# PERIPHERAL.net
KiCad netlist of a schematic drawn in Altium Designer
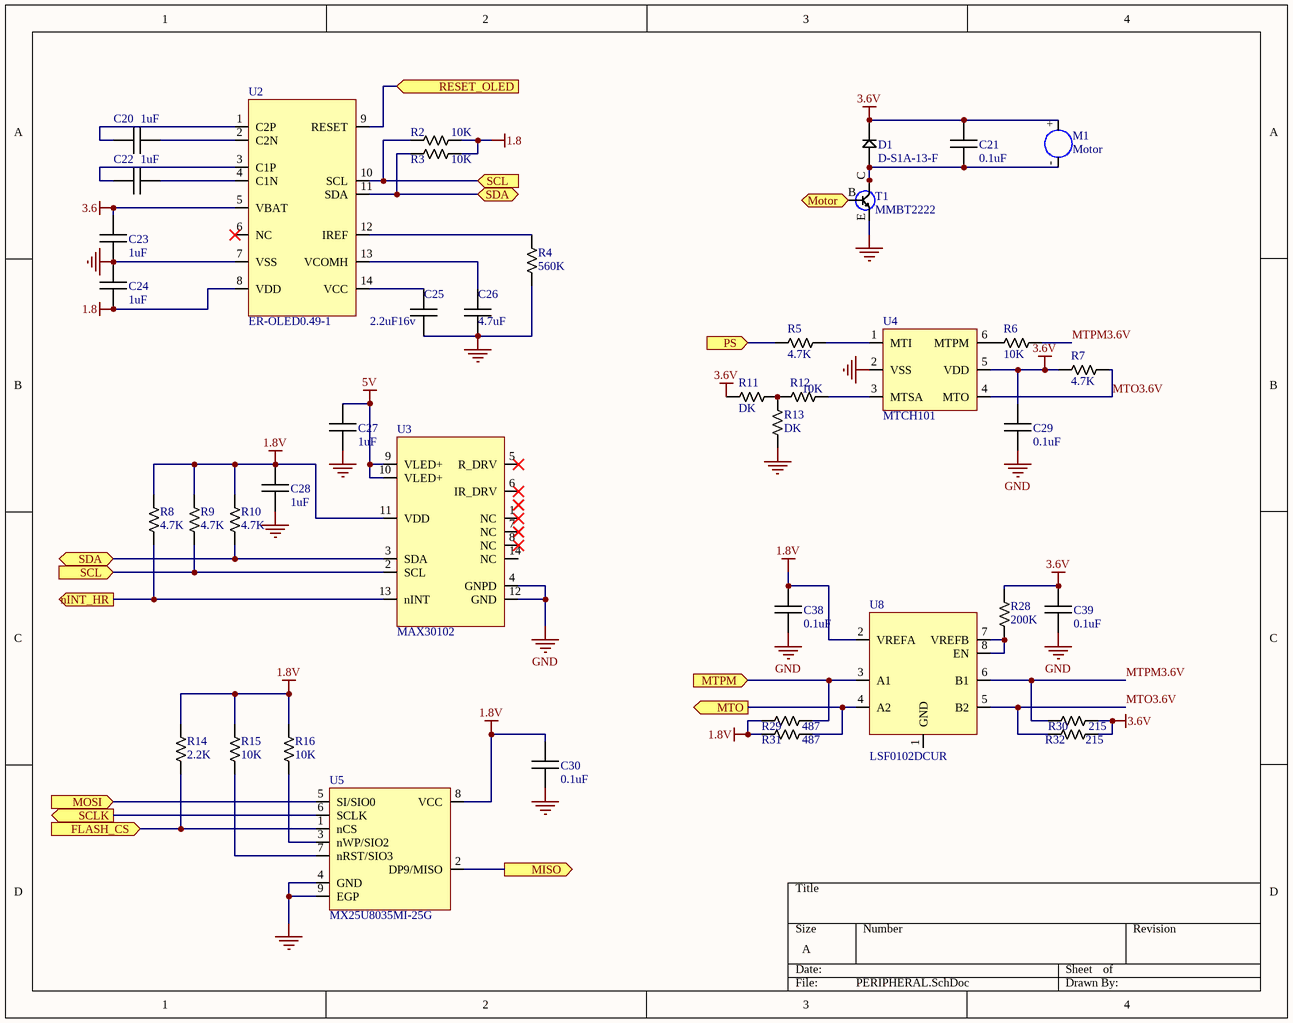
[diagram p0: PERIPHERAL.SchDoc]

(export (version "E")
  (design (tool "Eeschema 10.0.6"))
  (components
    (comp (ref "C20")
      (value "1uF")
      (description "SMD_CAPACITOR")
      (fields (field (name "DIGI-KEY PART NUMBER") "490-3890-1-ND") (field (name "TOLERANCE") "±10%"))
      (libsource (lib "test") (part "C1uF_0402"))
    )
    (comp (ref "C21")
      (value "0.1uF")
      (description "SMD_CAPACITOR")
      (fields (field (name "DIGI-KEY PART NUMBER") "490-6319-1-ND") (field (name "TOLERANCE") "±10%"))
      (libsource (lib "test") (part "C0.1uF_0402"))
    )
    (comp (ref "C22")
      (value "1uF")
      (description "SMD_CAPACITOR")
      (fields (field (name "DIGI-KEY PART NUMBER") "490-3890-1-ND") (field (name "TOLERANCE") "±10%"))
      (libsource (lib "test") (part "C1uF_0402"))
    )
    (comp (ref "C23")
      (value "1uF")
      (description "SMD_CAPACITOR")
      (fields (field (name "DIGI-KEY PART NUMBER") "490-3890-1-ND") (field (name "TOLERANCE") "±10%"))
      (libsource (lib "test") (part "C1uF_0402"))
    )
    (comp (ref "C24")
      (value "1uF")
      (description "SMD_CAPACITOR")
      (fields (field (name "DIGI-KEY PART NUMBER") "490-3890-1-ND") (field (name "TOLERANCE") "±10%"))
      (libsource (lib "test") (part "C1uF_0402"))
    )
    (comp (ref "C25")
      (value "2.2uF16v")
      (description "SMD_CAPACITOR")
      (fields (field (name "DIGI-KEY PART NUMBER") "490-3906-1-ND") (field (name "TOLERANCE") "±10%"))
      (libsource (lib "HR_lib") (part "C2.2uF_0805"))
    )
    (comp (ref "C26")
      (value "4.7uF")
      (description "SMD_CAPACITOR")
      (fields (field (name "DIGI-KEY PART NUMBER") "445-1385-1-ND") (field (name "TOLERANCE") "±10%"))
      (libsource (lib "HR_lib") (part "C4.7uF_0805"))
    )
    (comp (ref "C27")
      (value "1uF")
      (description "SMD_CAPACITOR")
      (fields (field (name "DIGI-KEY PART NUMBER") "490-3890-1-ND") (field (name "TOLERANCE") "±10%"))
      (libsource (lib "test") (part "C1uF_0402"))
    )
    (comp (ref "C28")
      (value "1uF")
      (description "SMD_CAPACITOR")
      (fields (field (name "DIGI-KEY PART NUMBER") "490-3890-1-ND") (field (name "TOLERANCE") "±10%"))
      (libsource (lib "test") (part "C1uF_0402"))
    )
    (comp (ref "C29")
      (value "0.1uF")
      (description "SMD_CAPACITOR")
      (fields (field (name "DIGI-KEY PART NUMBER") "490-6319-1-ND") (field (name "TOLERANCE") "±10%"))
      (libsource (lib "test") (part "C0.1uF_0402"))
    )
    (comp (ref "C30")
      (value "0.1uF")
      (description "SMD_CAPACITOR")
      (fields (field (name "DIGI-KEY PART NUMBER") "490-6319-1-ND") (field (name "TOLERANCE") "±10%"))
      (libsource (lib "test") (part "C0.1uF_0402"))
    )
    (comp (ref "C38")
      (value "0.1uF")
      (description "SMD_CAPACITOR")
      (fields (field (name "DIGI-KEY PART NUMBER") "490-6319-1-ND") (field (name "TOLERANCE") "±10%"))
      (libsource (lib "test") (part "C0.1uF_0402"))
    )
    (comp (ref "C39")
      (value "0.1uF")
      (description "SMD_CAPACITOR")
      (fields (field (name "DIGI-KEY PART NUMBER") "490-6319-1-ND") (field (name "TOLERANCE") "±10%"))
      (libsource (lib "test") (part "C0.1uF_0402"))
    )
    (comp (ref "D1")
      (value "D-S1A-13-F")
      (description "DIODE GEN PURP 50V 1A SMA")
      (libsource (lib "HR_lib") (part "D-S1A-13-F"))
    )
    (comp (ref "M1")
      (value "Motor")
      (description "vibrator coin 7mm")
      (fields (field (name "DIGI-KEY PART NUMBER") "1670-1000-ND"))
      (libsource (lib "HR_lib") (part "Motor"))
    )
    (comp (ref "R2")
      (value "10K")
      (footprint "R0603")
      (description "SMD_RESISTOR")
      (fields (field (name "DIGI-KEY PART NUMBER") "311-10KNCT-ND") (field (name "TOLERANCE") "±5%"))
      (libsource (lib "test") (part "R10K_0201"))
    )
    (comp (ref "R3")
      (value "10K")
      (footprint "R0603")
      (description "SMD_RESISTOR")
      (fields (field (name "DIGI-KEY PART NUMBER") "311-10KNCT-ND") (field (name "TOLERANCE") "±5%"))
      (libsource (lib "test") (part "R10K_0201"))
    )
    (comp (ref "R4")
      (value "560K")
      (footprint "R0603")
      (description "SMD_RESISTOR")
      (fields (field (name "DIGI-KEY PART NUMBER") "311-560KJRCT-ND") (field (name "TOLERANCE") "±5%"))
      (libsource (lib "test") (part "R560K_0402"))
    )
    (comp (ref "R5")
      (value "4.7K")
      (footprint "0603:R0603")
      (description "SMD_RESISTOR")
      (fields (field (name "DIGI-KEY PART NUMBER") "311-4.7KLRCT-ND") (field (name "TOLERANCE") "±1%"))
      (libsource (lib "HR_lib") (part "R4.7K_0402"))
    )
    (comp (ref "R6")
      (value "10K")
      (footprint "0603:R0603")
      (description "SMD_RESISTOR")
      (fields (field (name "DIGI-KEY PART NUMBER") "311-10KNCT-ND") (field (name "TOLERANCE") "±5%"))
      (libsource (lib "HR_lib") (part "R10K_0201"))
    )
    (comp (ref "R7")
      (value "4.7K")
      (footprint "0603:R0603")
      (description "SMD_RESISTOR")
      (fields (field (name "DIGI-KEY PART NUMBER") "311-4.7KLRCT-ND") (field (name "TOLERANCE") "±1%"))
      (libsource (lib "HR_lib") (part "R4.7K_0402"))
    )
    (comp (ref "R8")
      (value "4.7K")
      (footprint "0603:R0603")
      (description "SMD_RESISTOR")
      (fields (field (name "DIGI-KEY PART NUMBER") "311-4.7KLRCT-ND") (field (name "TOLERANCE") "±1%"))
      (libsource (lib "HR_lib") (part "R4.7K_0402"))
    )
    (comp (ref "R9")
      (value "4.7K")
      (footprint "0603:R0603")
      (description "SMD_RESISTOR")
      (fields (field (name "DIGI-KEY PART NUMBER") "311-4.7KLRCT-ND") (field (name "TOLERANCE") "±1%"))
      (libsource (lib "HR_lib") (part "R4.7K_0402"))
    )
    (comp (ref "R10")
      (value "4.7K")
      (footprint "0603:R0603")
      (description "SMD_RESISTOR")
      (fields (field (name "DIGI-KEY PART NUMBER") "311-4.7KLRCT-ND") (field (name "TOLERANCE") "±1%"))
      (libsource (lib "HR_lib") (part "R4.7K_0402"))
    )
    (comp (ref "R11")
      (value "DK")
      (footprint "0603:R0603")
      (description "SMD_RESISTOR")
      (libsource (lib "HR_lib") (part "RDK_0402"))
    )
    (comp (ref "R12")
      (value "10K")
      (footprint "0603:R0603")
      (description "SMD_RESISTOR")
      (fields (field (name "DIGI-KEY PART NUMBER") "311-10KNCT-ND") (field (name "TOLERANCE") "±5%"))
      (libsource (lib "HR_lib") (part "R10K_0201"))
    )
    (comp (ref "R13")
      (value "DK")
      (footprint "0603:R0603")
      (description "SMD_RESISTOR")
      (libsource (lib "HR_lib") (part "RDK_0402"))
    )
    (comp (ref "R14")
      (value "2.2K")
      (description "SMD_RESISTOR")
      (fields (field (name "DIGI-KEY PART NUMBER") "311-2.20KLRCT-ND") (field (name "TOLERANCE") "±1%"))
      (libsource (lib "HR_lib") (part "R2.2K_0402"))
    )
    (comp (ref "R15")
      (value "10K")
      (footprint "R0603")
      (description "SMD_RESISTOR")
      (fields (field (name "DIGI-KEY PART NUMBER") "311-10KNCT-ND") (field (name "TOLERANCE") "±5%"))
      (libsource (lib "test") (part "R10K_0201"))
    )
    (comp (ref "R16")
      (value "10K")
      (footprint "R0603")
      (description "SMD_RESISTOR")
      (fields (field (name "DIGI-KEY PART NUMBER") "311-10KNCT-ND") (field (name "TOLERANCE") "±5%"))
      (libsource (lib "test") (part "R10K_0201"))
    )
    (comp (ref "R28")
      (value "200K")
      (footprint "R0603")
      (description "SMD_RESISTOR")
      (fields (field (name "DIGI-KEY PART NUMBER") "541-200KAABCT-ND") (field (name "TOLERANCE") "±1%"))
      (libsource (lib "test") (part "R200K_0201"))
    )
    (comp (ref "R29")
      (value "487")
      (footprint "0603:R0603")
      (description "SMD_RESISTOR")
      (fields (field (name "DIGI-KEY PART NUMBER") "YAG2373CT-ND") (field (name "TOLERANCE") "±1%"))
      (libsource (lib "HR_lib") (part "R487_0402"))
    )
    (comp (ref "R30")
      (value "215")
      (footprint "0603:R0603")
      (description "SMD_RESISTOR")
      (fields (field (name "DIGI-KEY PART NUMBER") "YAG3056TR-ND") (field (name "TOLERANCE") "±1%"))
      (libsource (lib "HR_lib") (part "R215_0402"))
    )
    (comp (ref "R31")
      (value "487")
      (footprint "0603:R0603")
      (description "SMD_RESISTOR")
      (fields (field (name "DIGI-KEY PART NUMBER") "YAG2373CT-ND") (field (name "TOLERANCE") "±1%"))
      (libsource (lib "HR_lib") (part "R487_0402"))
    )
    (comp (ref "R32")
      (value "215")
      (footprint "0603:R0603")
      (description "SMD_RESISTOR")
      (fields (field (name "DIGI-KEY PART NUMBER") "YAG3056TR-ND") (field (name "TOLERANCE") "±1%"))
      (libsource (lib "HR_lib") (part "R215_0402"))
    )
    (comp (ref "T1")
      (value "MMBT2222")
      (description "SMD_Transistor")
      (fields (field (name "DIGI-KEY PART NUMBER") "MMBT2222ALT1GOSCT-ND"))
      (libsource (lib "HR_lib") (part "MMBT2222"))
    )
    (comp (ref "U2")
      (value "ER-OLED0.49-1")
      (description "OLED0.49")
      (libsource (lib "test") (part "ER-OLED0.49-1"))
    )
    (comp (ref "U3")
      (value "MAX30102")
      (description "Heart rate")
      (fields (field (name "DIGI-KEY PART NUMBER") "MAX30102EFD+-ND"))
      (libsource (lib "HR_lib") (part "MAX30102"))
    )
    (comp (ref "U4")
      (value "MTCH101")
      (description "IC PROXIMITY DETECTOR SOT23-6")
      (fields (field (name "DIGI-KEY PART NUMBER") "MTCH101-I/OT-ND"))
      (libsource (lib "HR_lib") (part "MTCH101"))
    )
    (comp (ref "U5")
      (value "MX25U8035MI-25G")
      (description "IC FLASH 8MBIT 40MHZ 8SOP")
      (fields (field (name "DIGI-KEY PART NUMBER") "1092-1119-ND"))
      (libsource (lib "HR_lib") (part "MX25U8035MI-25G"))
    )
    (comp (ref "U8")
      (value "LSF0102DCUR")
      (description "IC LEVEL TRANSLATOR BIDIR US8")
      (fields (field (name "DIGI-KEY PART NUMBER") "296-39070-1-ND"))
      (libsource (lib "HR_lib") (part "LSF0102DCUR"))
    )
  )
  (nets
    (net (code "1") (name "/FLASH_CS") (class "Default")
      (node (ref "R14") (pin "1") (pintype "passive"))
      (node (ref "U5") (pin "1") (pinfunction "nCS_1") (pintype "passive"))
    )
    (net (code "2") (name "/MISO") (class "Default")
      (node (ref "U5") (pin "2") (pinfunction "DP9/MISO_2") (pintype "passive"))
    )
    (net (code "3") (name "/MOSI") (class "Default")
      (node (ref "U5") (pin "5") (pinfunction "SI/SIO0_5") (pintype "passive"))
    )
    (net (code "4") (name "/MTO") (class "Default")
      (node (ref "R31") (pin "1") (pintype "passive"))
      (node (ref "U8") (pin "4") (pinfunction "A2_4") (pintype "passive"))
    )
    (net (code "5") (name "/MTO3.6V") (class "Default")
      (node (ref "R32") (pin "1") (pintype "passive"))
      (node (ref "R7") (pin "1") (pintype "passive"))
      (node (ref "U4") (pin "4") (pinfunction "MTO_4") (pintype "passive"))
      (node (ref "U8") (pin "5") (pinfunction "B2_5") (pintype "passive"))
    )
    (net (code "6") (name "/MTPM") (class "Default")
      (node (ref "R29") (pin "1") (pintype "passive"))
      (node (ref "U8") (pin "3") (pinfunction "A1_3") (pintype "passive"))
    )
    (net (code "7") (name "/MTPM3.6V") (class "Default")
      (node (ref "R30") (pin "1") (pintype "passive"))
      (node (ref "R6") (pin "2") (pintype "passive"))
      (node (ref "U8") (pin "6") (pinfunction "B1_6") (pintype "passive"))
    )
    (net (code "8") (name "/Motor") (class "Default")
      (node (ref "T1") (pin "B") (pinfunction "B_B") (pintype "passive"))
    )
    (net (code "9") (name "/PS") (class "Default") (node (ref "R5") (pin "1") (pintype "passive")))
    (net (code "10") (name "/RESET_OLED") (class "Default")
      (node (ref "U2") (pin "9") (pinfunction "RESET_9") (pintype "passive"))
    )
    (net (code "11") (name "/SCL") (class "Default")
      (node (ref "R2") (pin "2") (pintype "passive"))
      (node (ref "R9") (pin "1") (pintype "passive"))
      (node (ref "U2") (pin "10") (pinfunction "SCL_10") (pintype "passive"))
      (node (ref "U3") (pin "2") (pinfunction "SCL_2") (pintype "passive"))
    )
    (net (code "12") (name "/SCLK") (class "Default")
      (node (ref "U5") (pin "6") (pinfunction "SCLK_6") (pintype "passive"))
    )
    (net (code "13") (name "/SDA") (class "Default")
      (node (ref "R10") (pin "1") (pintype "passive"))
      (node (ref "R3") (pin "2") (pintype "passive"))
      (node (ref "U2") (pin "11") (pinfunction "SDA_11") (pintype "passive"))
      (node (ref "U3") (pin "3") (pinfunction "SDA_3") (pintype "passive"))
    )
    (net (code "14") (name "/nINT_HR") (class "Default")
      (node (ref "R8") (pin "1") (pintype "passive"))
      (node (ref "U3") (pin "13") (pinfunction "nINT_13") (pintype "passive"))
    )
    (net (code "15") (name "1.8") (class "Default")
      (node (ref "C24") (pin "2") (pintype "passive"))
      (node (ref "R2") (pin "1") (pintype "passive"))
      (node (ref "R3") (pin "1") (pintype "passive"))
      (node (ref "U2") (pin "8") (pinfunction "VDD_8") (pintype "passive"))
    )
    (net (code "16") (name "1.8V") (class "Default")
      (node (ref "C28") (pin "2") (pintype "passive"))
      (node (ref "C30") (pin "2") (pintype "passive"))
      (node (ref "C38") (pin "2") (pintype "passive"))
      (node (ref "R10") (pin "2") (pintype "passive"))
      (node (ref "R14") (pin "2") (pintype "passive"))
      (node (ref "R15") (pin "2") (pintype "passive"))
      (node (ref "R16") (pin "2") (pintype "passive"))
      (node (ref "R29") (pin "2") (pintype "passive"))
      (node (ref "R31") (pin "2") (pintype "passive"))
      (node (ref "R8") (pin "2") (pintype "passive"))
      (node (ref "R9") (pin "2") (pintype "passive"))
      (node (ref "U3") (pin "11") (pinfunction "VDD_11") (pintype "passive"))
      (node (ref "U5") (pin "8") (pinfunction "VCC_8") (pintype "passive"))
      (node (ref "U8") (pin "2") (pinfunction "VREFA_2") (pintype "passive"))
    )
    (net (code "17") (name "3.6") (class "Default")
      (node (ref "C23") (pin "2") (pintype "passive"))
      (node (ref "U2") (pin "5") (pinfunction "VBAT_5") (pintype "passive"))
    )
    (net (code "18") (name "3.6V") (class "Default")
      (node (ref "C21") (pin "2") (pintype "passive"))
      (node (ref "C29") (pin "2") (pintype "passive"))
      (node (ref "C39") (pin "2") (pintype "passive"))
      (node (ref "D1") (pin "1") (pinfunction "-_1") (pintype "passive"))
      (node (ref "M1") (pin "+") (pinfunction "+_+") (pintype "passive"))
      (node (ref "R11") (pin "1") (pintype "passive"))
      (node (ref "R28") (pin "2") (pintype "passive"))
      (node (ref "R30") (pin "2") (pintype "passive"))
      (node (ref "R32") (pin "2") (pintype "passive"))
      (node (ref "R7") (pin "2") (pintype "passive"))
      (node (ref "U4") (pin "5") (pinfunction "VDD_5") (pintype "passive"))
    )
    (net (code "19") (name "5V") (class "Default")
      (node (ref "C27") (pin "2") (pintype "passive"))
      (node (ref "U3") (pin "10") (pinfunction "VLED+_10") (pintype "passive"))
      (node (ref "U3") (pin "9") (pinfunction "VLED+_9") (pintype "passive"))
    )
    (net (code "20") (name "GND") (class "Default")
      (node (ref "C23") (pin "1") (pintype "passive"))
      (node (ref "C24") (pin "1") (pintype "passive"))
      (node (ref "C25") (pin "1") (pintype "passive"))
      (node (ref "C26") (pin "1") (pintype "passive"))
      (node (ref "C27") (pin "1") (pintype "passive"))
      (node (ref "C28") (pin "1") (pintype "passive"))
      (node (ref "C29") (pin "1") (pintype "passive"))
      (node (ref "C30") (pin "1") (pintype "passive"))
      (node (ref "C38") (pin "1") (pintype "passive"))
      (node (ref "C39") (pin "1") (pintype "passive"))
      (node (ref "R13") (pin "1") (pintype "passive"))
      (node (ref "R4") (pin "1") (pintype "passive"))
      (node (ref "T1") (pin "E") (pinfunction "E_E") (pintype "passive"))
      (node (ref "U2") (pin "7") (pinfunction "VSS_7") (pintype "passive"))
      (node (ref "U3") (pin "12") (pinfunction "GND_12") (pintype "passive"))
      (node (ref "U3") (pin "4") (pinfunction "GNPD_4") (pintype "passive"))
      (node (ref "U4") (pin "2") (pinfunction "VSS_2") (pintype "passive"))
      (node (ref "U5") (pin "4") (pinfunction "GND_4") (pintype "passive"))
      (node (ref "U5") (pin "9") (pinfunction "EGP_9") (pintype "passive"))
    )
    (net (code "21") (name "Net-(D1-+)") (class "Default")
      (node (ref "C21") (pin "1") (pintype "passive"))
      (node (ref "D1") (pin "2") (pinfunction "+_2") (pintype "passive"))
      (node (ref "M1") (pin "-") (pinfunction "-_-") (pintype "passive"))
      (node (ref "T1") (pin "C") (pinfunction "C_C") (pintype "passive"))
    )
    (net (code "22") (name "Net-(R11-Pad2)") (class "Default")
      (node (ref "R11") (pin "2") (pintype "passive"))
      (node (ref "R12") (pin "1") (pintype "passive"))
      (node (ref "R13") (pin "2") (pintype "passive"))
    )
    (net (code "23") (name "Net-(U2-C1N)") (class "Default")
      (node (ref "C22") (pin "1") (pintype "passive"))
      (node (ref "U2") (pin "4") (pinfunction "C1N_4") (pintype "passive"))
    )
    (net (code "24") (name "Net-(U2-C1P)") (class "Default")
      (node (ref "C22") (pin "2") (pintype "passive"))
      (node (ref "U2") (pin "3") (pinfunction "C1P_3") (pintype "passive"))
    )
    (net (code "25") (name "Net-(U2-C2N)") (class "Default")
      (node (ref "C20") (pin "1") (pintype "passive"))
      (node (ref "U2") (pin "2") (pinfunction "C2N_2") (pintype "passive"))
    )
    (net (code "26") (name "Net-(U2-C2P)") (class "Default")
      (node (ref "C20") (pin "2") (pintype "passive"))
      (node (ref "U2") (pin "1") (pinfunction "C2P_1") (pintype "passive"))
    )
    (net (code "27") (name "Net-(U2-IREF)") (class "Default")
      (node (ref "R4") (pin "2") (pintype "passive"))
      (node (ref "U2") (pin "12") (pinfunction "IREF_12") (pintype "passive"))
    )
    (net (code "28") (name "Net-(U2-VCC)") (class "Default")
      (node (ref "C25") (pin "2") (pintype "passive"))
      (node (ref "U2") (pin "14") (pinfunction "VCC_14") (pintype "passive"))
    )
    (net (code "29") (name "Net-(U2-VCOMH)") (class "Default")
      (node (ref "C26") (pin "2") (pintype "passive"))
      (node (ref "U2") (pin "13") (pinfunction "VCOMH_13") (pintype "passive"))
    )
    (net (code "30") (name "Net-(U4-MTI)") (class "Default")
      (node (ref "R5") (pin "2") (pintype "passive"))
      (node (ref "U4") (pin "1") (pinfunction "MTI_1") (pintype "passive"))
    )
    (net (code "31") (name "Net-(U4-MTPM)") (class "Default")
      (node (ref "R6") (pin "1") (pintype "passive"))
      (node (ref "U4") (pin "6") (pinfunction "MTPM_6") (pintype "passive"))
    )
    (net (code "32") (name "Net-(U4-MTSA)") (class "Default")
      (node (ref "R12") (pin "2") (pintype "passive"))
      (node (ref "U4") (pin "3") (pinfunction "MTSA_3") (pintype "passive"))
    )
    (net (code "33") (name "Net-(U5-nRST{slash}SIO3)") (class "Default")
      (node (ref "R15") (pin "1") (pintype "passive"))
      (node (ref "U5") (pin "7") (pinfunction "nRST/SIO3_7") (pintype "passive"))
    )
    (net (code "34") (name "Net-(U5-nWP{slash}SIO2)") (class "Default")
      (node (ref "R16") (pin "1") (pintype "passive"))
      (node (ref "U5") (pin "3") (pinfunction "nWP/SIO2_3") (pintype "passive"))
    )
    (net (code "35") (name "Net-(U8-EN)") (class "Default")
      (node (ref "R28") (pin "1") (pintype "passive"))
      (node (ref "U8") (pin "7") (pinfunction "VREFB_7") (pintype "passive"))
      (node (ref "U8") (pin "8") (pinfunction "EN_8") (pintype "passive"))
    )
    (net (code "36") (name "unconnected-(U2-NC-Pad6)") (class "Default")
      (node (ref "U2") (pin "6") (pinfunction "NC_6") (pintype "passive+no_connect"))
    )
    (net (code "37") (name "unconnected-(U3-IR_DRV-Pad6)") (class "Default")
      (node (ref "U3") (pin "6") (pinfunction "IR_DRV_6") (pintype "passive+no_connect"))
    )
    (net (code "38") (name "unconnected-(U3-NC-Pad1)") (class "Default")
      (node (ref "U3") (pin "1") (pinfunction "NC_1") (pintype "passive+no_connect"))
    )
    (net (code "39") (name "unconnected-(U3-NC-Pad7)") (class "Default")
      (node (ref "U3") (pin "7") (pinfunction "NC_7") (pintype "passive+no_connect"))
    )
    (net (code "40") (name "unconnected-(U3-NC-Pad8)") (class "Default")
      (node (ref "U3") (pin "8") (pinfunction "NC_8") (pintype "passive+no_connect"))
    )
    (net (code "41") (name "unconnected-(U3-NC-Pad14)") (class "Default")
      (node (ref "U3") (pin "14") (pinfunction "NC_14") (pintype "passive"))
    )
    (net (code "42") (name "unconnected-(U3-R_DRV-Pad5)") (class "Default")
      (node (ref "U3") (pin "5") (pinfunction "R_DRV_5") (pintype "passive+no_connect"))
    )
    (net (code "43") (name "unconnected-(U8-GND-Pad1)") (class "Default")
      (node (ref "U8") (pin "1") (pinfunction "GND_1") (pintype "passive"))
    )
  )
)
